# design.net
KiCad netlist of a schematic drawn in Altium Designer
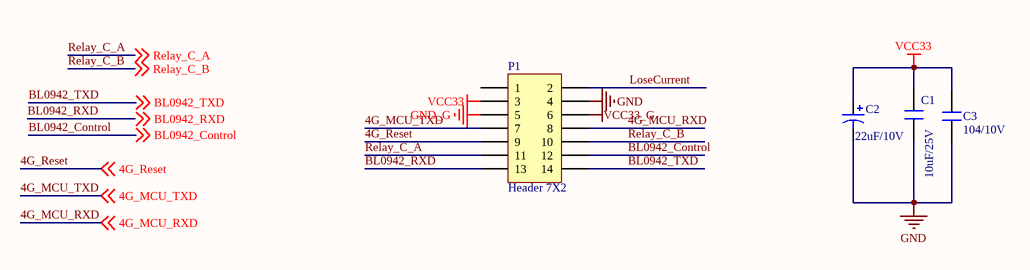
[diagram p0: 连接.SchDoc]

(export (version "E")
  (design (tool "Eeschema 10.0.6"))
  (components
    (comp (ref "C1") (value "10uF/25V") (footprint "0603R") (libsource (lib "ES_Schematic") (part "CAP")))
    (comp (ref "C2")
      (value "22uF/10V")
      (footprint "0805R")
      (description "Polarized Capacitor (Radial)")
      (fields (field (name "PUBLISHER") "Altium Limited"))
      (libsource (lib "Miscellaneous Devices") (part "Cap Pol1"))
    )
    (comp (ref "C3") (value "104/10V") (footprint "0603R") (libsource (lib "ES_Schematic") (part "CAP_1")))
    (comp (ref "P1")
      (value "Header 7X2")
      (footprint "HDR2X7")
      (description "Header, 7-Pin, Dual row")
      (fields (field (name "PUBLISHER") "Altium Limited"))
      (libsource (lib "Miscellaneous Connectors") (part "Header 7X2"))
    )
  )
  (nets
    (net (code "1") (name "/LoseCurrent") (class "Default")
      (node (ref "P1") (pin "2") (pinfunction "2_2") (pintype "passive"))
    )
    (net (code "2") (name "4G_MCU_RXD") (class "Default")
      (node (ref "P1") (pin "8") (pinfunction "8_8") (pintype "passive"))
    )
    (net (code "3") (name "4G_MCU_TXD") (class "Default")
      (node (ref "P1") (pin "7") (pinfunction "7_7") (pintype "passive"))
    )
    (net (code "4") (name "4G_Reset") (class "Default")
      (node (ref "P1") (pin "9") (pinfunction "9_9") (pintype "passive"))
    )
    (net (code "5") (name "BL0942_Control") (class "Default")
      (node (ref "P1") (pin "12") (pinfunction "12_12") (pintype "passive"))
    )
    (net (code "6") (name "BL0942_RXD") (class "Default")
      (node (ref "P1") (pin "13") (pinfunction "13_13") (pintype "passive"))
    )
    (net (code "7") (name "BL0942_TXD") (class "Default")
      (node (ref "P1") (pin "14") (pinfunction "14_14") (pintype "passive"))
    )
    (net (code "8") (name "GND") (class "Default")
      (node (ref "C1") (pin "1") (pinfunction "1_1") (pintype "passive"))
      (node (ref "C2") (pin "2") (pinfunction "2_2") (pintype "passive"))
      (node (ref "C3") (pin "1") (pinfunction "1_1") (pintype "passive"))
      (node (ref "P1") (pin "4") (pinfunction "4_4") (pintype "passive"))
    )
    (net (code "9") (name "GND_G") (class "Default")
      (node (ref "P1") (pin "5") (pinfunction "5_5") (pintype "passive"))
    )
    (net (code "10") (name "Relay_C_A") (class "Default")
      (node (ref "P1") (pin "11") (pinfunction "11_11") (pintype "passive"))
    )
    (net (code "11") (name "Relay_C_B") (class "Default")
      (node (ref "P1") (pin "10") (pinfunction "10_10") (pintype "passive"))
    )
    (net (code "12") (name "VCC33") (class "Default")
      (node (ref "C1") (pin "2") (pinfunction "2_2") (pintype "passive"))
      (node (ref "C2") (pin "1") (pinfunction "1_1") (pintype "passive"))
      (node (ref "C3") (pin "2") (pinfunction "2_2") (pintype "passive"))
      (node (ref "P1") (pin "3") (pinfunction "3_3") (pintype "passive"))
    )
    (net (code "13") (name "VCC33_G") (class "Default")
      (node (ref "P1") (pin "6") (pinfunction "6_6") (pintype "passive"))
    )
    (net (code "14") (name "unconnected-(P1-Pad1)") (class "Default")
      (node (ref "P1") (pin "1") (pinfunction "1_1") (pintype "passive"))
    )
  )
)
